# RX_Pre.net
KiCad netlist of a schematic drawn in Altium Designer
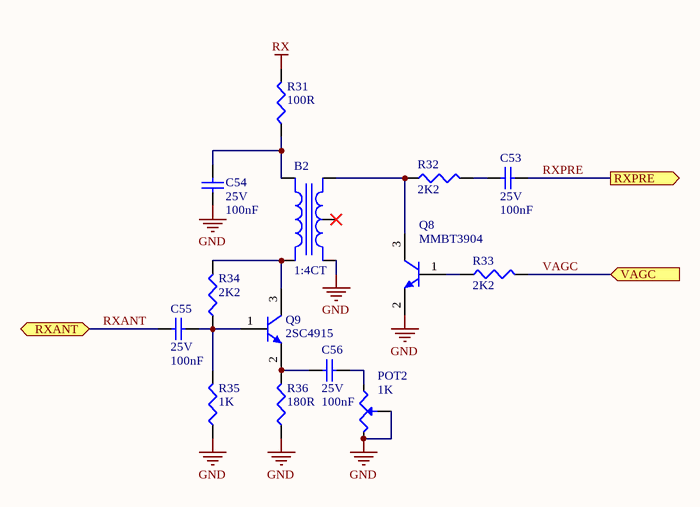
[diagram p0: RX_Pre.SchDoc]

(export (version "E")
  (design (tool "Eeschema 10.0.6"))
  (components
    (comp (ref "B2")
      (value "1:4CT")
      (footprint "CX2047LANL")
      (description "Balun 4CT:1")
      (libsource (lib "NavarroIND") (part "BALUN CX2047LANL"))
    )
    (comp (ref "C53")
      (value "100nF")
      (footprint "CC0603")
      (description "Capacitor (Semiconductor SIM Model)")
      (fields (field (name "TENSÃO") "25V") (field (name "Comment") "Capacitor Cerâmico"))
      (libsource (lib "NavarroCAP") (part "Cap 100nF 25V 0603 X7R"))
    )
    (comp (ref "C54")
      (value "100nF")
      (footprint "CC0603")
      (description "Capacitor (Semiconductor SIM Model)")
      (fields (field (name "TENSÃO") "25V") (field (name "Comment") "Capacitor Cerâmico"))
      (libsource (lib "NavarroCAP") (part "Cap 100nF 25V 0603 X7R"))
    )
    (comp (ref "C55")
      (value "100nF")
      (footprint "CC0603")
      (description "Capacitor (Semiconductor SIM Model)")
      (fields (field (name "TENSÃO") "25V") (field (name "Comment") "Capacitor Cerâmico"))
      (libsource (lib "NavarroCAP") (part "Cap 100nF 25V 0603 X7R"))
    )
    (comp (ref "C56")
      (value "100nF")
      (footprint "CC0603")
      (description "Capacitor (Semiconductor SIM Model)")
      (fields (field (name "TENSÃO") "25V") (field (name "Comment") "Capacitor Cerâmico"))
      (libsource (lib "NavarroCAP") (part "Cap 100nF 25V 0603 X7R"))
    )
    (comp (ref "POT2")
      (value "1K")
      (footprint "POT - PTV09")
      (description "Potenciometro")
      (fields (field (name "Comment") "Potenciômetro"))
      (libsource (lib "NavarroRES") (part "POT 100k Audio"))
    )
    (comp (ref "Q8")
      (value "MMBT3904")
      (footprint "SOT-23-3N")
      (description "NPN General Purpose Amplifier")
      (libsource (lib "NavarroSEMI") (part "TRS MMBT3904 40V 200mA SOT-23-3N"))
    )
    (comp (ref "Q9")
      (value "2SC4915")
      (footprint "SOT-23-3N")
      (description "NPN General Purpose Amplifier")
      (libsource (lib "NavarroSEMI") (part "TRS 2SC3324 120V 100mA SOT-23-3"))
    )
    (comp (ref "R31")
      (value "100R")
      (footprint "CC0603")
      (description "Resistor")
      (libsource (lib "NavarroRES") (part "Res 100R 5% 0603 1/10W"))
    )
    (comp (ref "R32")
      (value "2K2")
      (footprint "CC0603")
      (description "Resistor")
      (libsource (lib "NavarroRES") (part "Res 2K2 5% 0603 1/10W"))
    )
    (comp (ref "R33")
      (value "2K2")
      (footprint "CC0603")
      (description "Resistor")
      (libsource (lib "NavarroRES") (part "Res 2K2 5% 0603 1/10W"))
    )
    (comp (ref "R34")
      (value "2K2")
      (footprint "CC0603")
      (description "Resistor")
      (libsource (lib "NavarroRES") (part "Res 2K2 5% 0603 1/10W"))
    )
    (comp (ref "R35")
      (value "1K")
      (footprint "CC0603")
      (description "Resistor")
      (libsource (lib "NavarroRES") (part "Res 1K 1% 0603 1/10W"))
    )
    (comp (ref "R36")
      (value "180R")
      (footprint "CC0603")
      (description "Resistor")
      (libsource (lib "NavarroRES") (part "Res 180R 1% 0603 1/10W"))
    )
  )
  (nets
    (net (code "1") (name "/RXANT") (class "Default")
      (node (ref "C55") (pin "2") (pinfunction "2_2") (pintype "passive"))
    )
    (net (code "2") (name "/RXPRE") (class "Default")
      (node (ref "C53") (pin "1") (pinfunction "1_1") (pintype "passive"))
    )
    (net (code "3") (name "/VAGC") (class "Default")
      (node (ref "R33") (pin "2") (pinfunction "2_2") (pintype "passive"))
    )
    (net (code "4") (name "GND") (class "Default")
      (node (ref "B2") (pin "3") (pinfunction "Pri-_3") (pintype "passive"))
      (node (ref "C54") (pin "1") (pinfunction "1_1") (pintype "passive"))
      (node (ref "POT2") (pin "2") (pinfunction "TAP_2") (pintype "passive"))
      (node (ref "POT2") (pin "3") (pinfunction "3_3") (pintype "passive"))
      (node (ref "Q8") (pin "2") (pinfunction "E_2") (pintype "passive"))
      (node (ref "R35") (pin "1") (pinfunction "1_1") (pintype "passive"))
      (node (ref "R36") (pin "1") (pinfunction "1_1") (pintype "passive"))
    )
    (net (code "5") (name "Net-(B2-Pri+)") (class "Default")
      (node (ref "B2") (pin "4") (pinfunction "Pri+_4") (pintype "passive"))
      (node (ref "Q9") (pin "3") (pinfunction "C_3") (pintype "passive"))
      (node (ref "R34") (pin "2") (pinfunction "2_2") (pintype "passive"))
    )
    (net (code "6") (name "Net-(B2-Sec-)") (class "Default")
      (node (ref "B2") (pin "6") (pinfunction "Sec-_6") (pintype "passive"))
      (node (ref "C54") (pin "2") (pinfunction "2_2") (pintype "passive"))
      (node (ref "R31") (pin "1") (pinfunction "1_1") (pintype "passive"))
    )
    (net (code "7") (name "Net-(C53-Pad2)") (class "Default")
      (node (ref "C53") (pin "2") (pinfunction "2_2") (pintype "passive"))
      (node (ref "R32") (pin "2") (pinfunction "2_2") (pintype "passive"))
    )
    (net (code "8") (name "Net-(C56-Pad1)") (class "Default")
      (node (ref "C56") (pin "1") (pinfunction "1_1") (pintype "passive"))
      (node (ref "POT2") (pin "1") (pinfunction "1_1") (pintype "passive"))
    )
    (net (code "9") (name "Net-(Q8-B)") (class "Default")
      (node (ref "Q8") (pin "1") (pinfunction "B_1") (pintype "passive"))
      (node (ref "R33") (pin "1") (pinfunction "1_1") (pintype "passive"))
    )
    (net (code "10") (name "Net-(Q8-C)") (class "Default")
      (node (ref "B2") (pin "1") (pinfunction "Sec+_1") (pintype "passive"))
      (node (ref "Q8") (pin "3") (pinfunction "C_3") (pintype "passive"))
      (node (ref "R32") (pin "1") (pinfunction "1_1") (pintype "passive"))
    )
    (net (code "11") (name "Net-(Q9-B)") (class "Default")
      (node (ref "C55") (pin "1") (pinfunction "1_1") (pintype "passive"))
      (node (ref "Q9") (pin "1") (pinfunction "B_1") (pintype "passive"))
      (node (ref "R34") (pin "1") (pinfunction "1_1") (pintype "passive"))
      (node (ref "R35") (pin "2") (pinfunction "2_2") (pintype "passive"))
    )
    (net (code "12") (name "Net-(Q9-E)") (class "Default")
      (node (ref "C56") (pin "2") (pinfunction "2_2") (pintype "passive"))
      (node (ref "Q9") (pin "2") (pinfunction "E_2") (pintype "passive"))
      (node (ref "R36") (pin "2") (pinfunction "2_2") (pintype "passive"))
    )
    (net (code "13") (name "RX") (class "Default")
      (node (ref "R31") (pin "2") (pinfunction "2_2") (pintype "passive"))
    )
    (net (code "14") (name "unconnected-(B2-Sec+-Pad2)") (class "Default")
      (node (ref "B2") (pin "2") (pinfunction "Sec+_2") (pintype "passive+no_connect"))
    )
  )
)
